# Sheet3_Audio_Out.net
KiCad netlist of a schematic drawn in Altium Designer
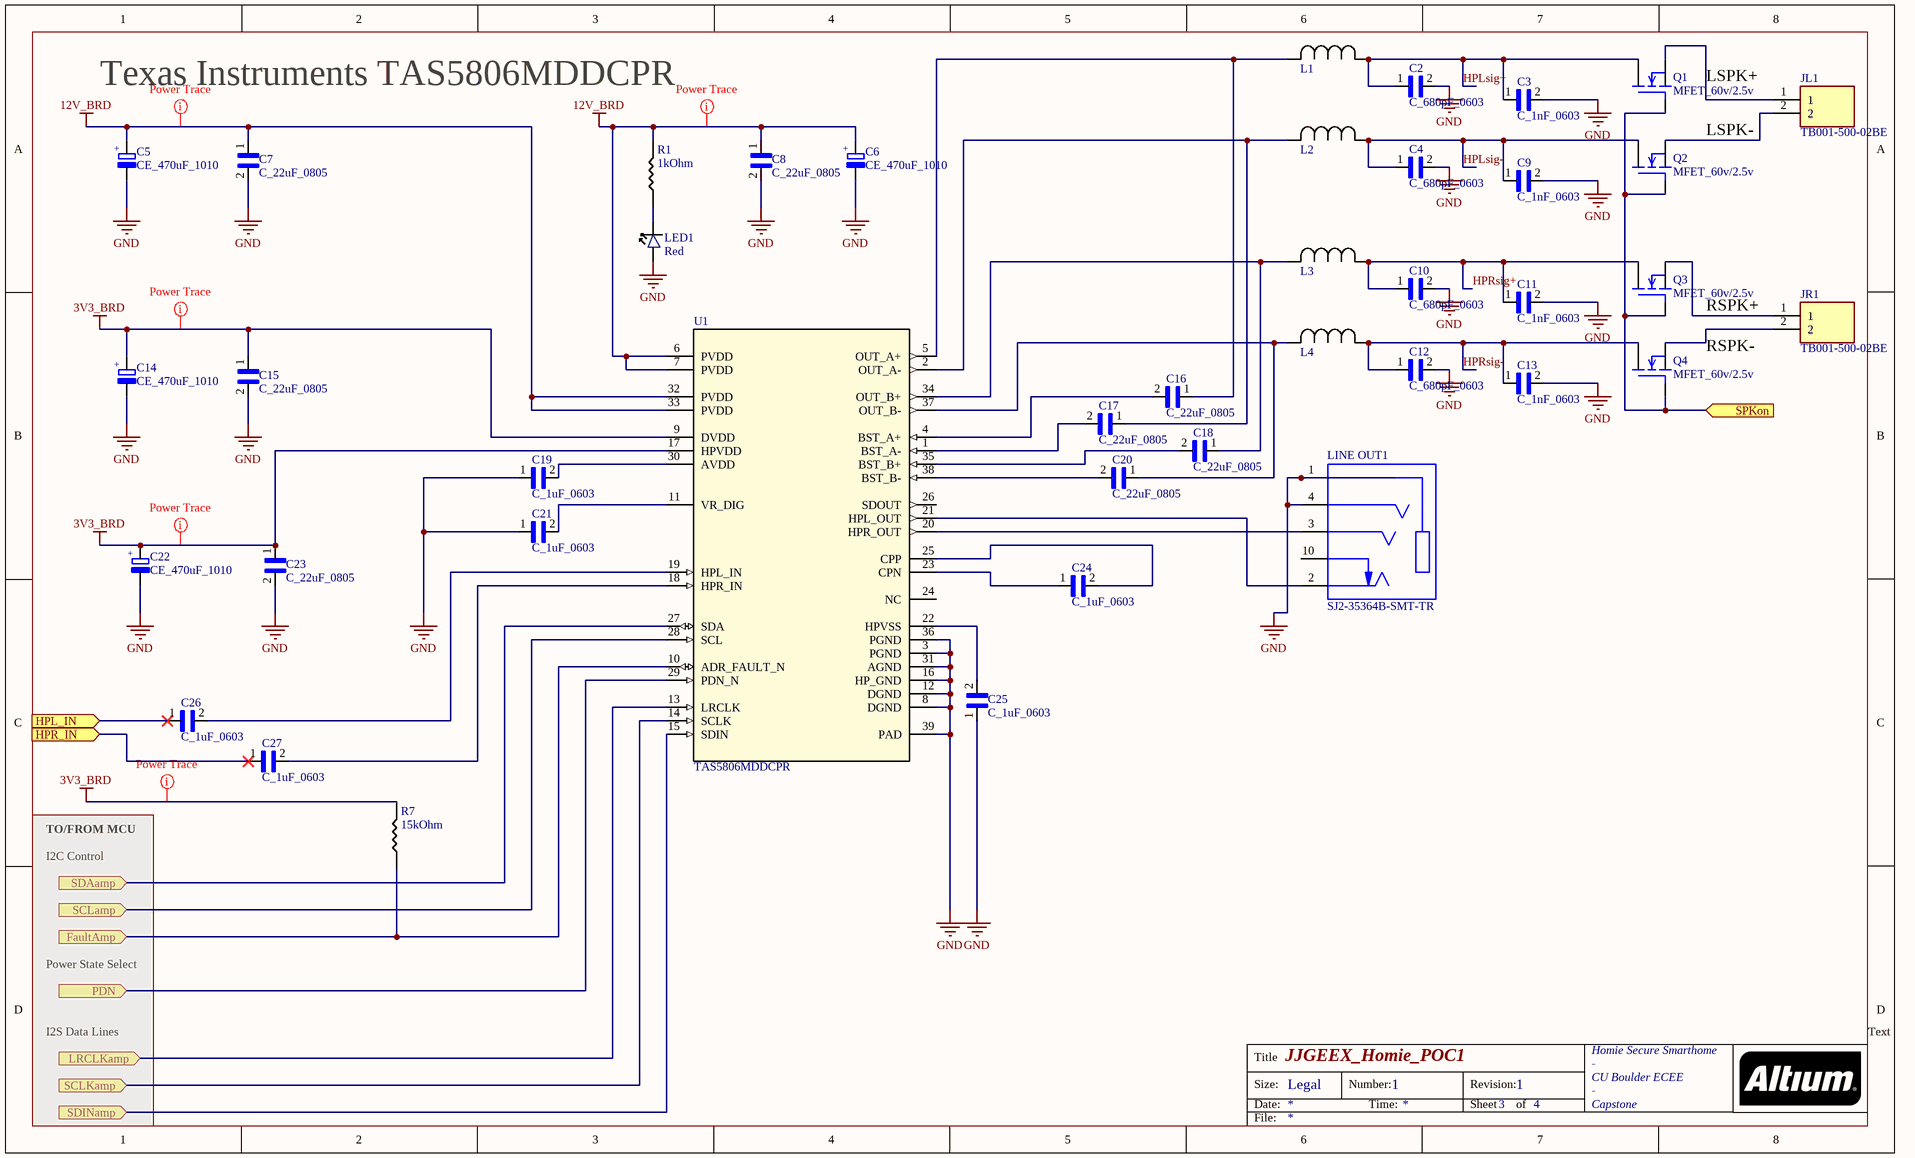
[diagram p0: Sheet3_Audio_Out.SchDoc]

(export (version "E")
  (design (tool "Eeschema 10.0.6"))
  (components
    (comp (ref "C2")
      (value "C_680pF_0603")
      (footprint "CAPC1608X90N")
      (description "680pF ±10% 50V Ceramic Capacitor X7R 0603 (1608 Metric)")
      (fields (field (name "MP") "CL10B684KO8NNNC") (field (name "MF") "Samsung"))
      (libsource (lib "Homie_IntegratedLibraryV2") (part "C_680pF_0603"))
    )
    (comp (ref "C3")
      (value "C_1nF_0603")
      (footprint "CAPC1608X90N")
      (description "1000pF ±10% 50V Ceramic Capacitor X7R 0603 (1608 Metric)")
      (fields (field (name "MP") "CL10B102KB8NNNC") (field (name "MF") "Samsung"))
      (libsource (lib "Homie_IntegratedLibraryV2") (part "C_1nF_0603"))
    )
    (comp (ref "C4")
      (value "C_680pF_0603")
      (footprint "CAPC1608X90N")
      (description "680pF ±10% 50V Ceramic Capacitor X7R 0603 (1608 Metric)")
      (fields (field (name "MP") "CL10B684KO8NNNC") (field (name "MF") "Samsung"))
      (libsource (lib "Homie_IntegratedLibraryV2") (part "C_680pF_0603"))
    )
    (comp (ref "C5")
      (value "CE_470uF_1010")
      (footprint "140CLH-1010")
      (description "Aluminum Electrolytic Capacitors - SMD")
      (fields (field (name "MP") "VZH471M1ETR-1010") (field (name "MF") "Lelon"))
      (libsource (lib "Homie_IntegratedLibraryV2") (part "CE_470uF_1010"))
    )
    (comp (ref "C6")
      (value "CE_470uF_1010")
      (footprint "140CLH-1010")
      (description "Aluminum Electrolytic Capacitors - SMD")
      (fields (field (name "MP") "VZH471M1ETR-1010") (field (name "MF") "Lelon"))
      (libsource (lib "Homie_IntegratedLibraryV2") (part "CE_470uF_1010"))
    )
    (comp (ref "C7")
      (value "C_22uF_0805")
      (footprint "CAPC2012X140N")
      (description "22µF 0805 ±20% 25V Ceramic Capacitor X5R 0805 (2012 Metric)")
      (fields (field (name "MF") "Samsung") (field (name "DIGI-KEY_PART_NUMBER") "1276-2908-1-ND"))
      (libsource (lib "") (part "C_22uF_0805_1"))
    )
    (comp (ref "C8")
      (value "C_22uF_0805")
      (footprint "CAPC2012X140N")
      (description "22µF 0805 ±20% 25V Ceramic Capacitor X5R 0805 (2012 Metric)")
      (fields (field (name "MF") "Samsung") (field (name "DIGI-KEY_PART_NUMBER") "1276-2908-1-ND"))
      (libsource (lib "") (part "C_22uF_0805_1"))
    )
    (comp (ref "C9")
      (value "C_1nF_0603")
      (footprint "CAPC1608X90N")
      (description "1000pF ±10% 50V Ceramic Capacitor X7R 0603 (1608 Metric)")
      (fields (field (name "MP") "CL10B102KB8NNNC") (field (name "MF") "Samsung"))
      (libsource (lib "Homie_IntegratedLibraryV2") (part "C_1nF_0603"))
    )
    (comp (ref "C10")
      (value "C_680pF_0603")
      (footprint "CAPC1608X90N")
      (description "680pF ±10% 50V Ceramic Capacitor X7R 0603 (1608 Metric)")
      (fields (field (name "MP") "CL10B684KO8NNNC") (field (name "MF") "Samsung"))
      (libsource (lib "Homie_IntegratedLibraryV2") (part "C_680pF_0603"))
    )
    (comp (ref "C11")
      (value "C_1nF_0603")
      (footprint "CAPC1608X90N")
      (description "1000pF ±10% 50V Ceramic Capacitor X7R 0603 (1608 Metric)")
      (fields (field (name "MP") "CL10B102KB8NNNC") (field (name "MF") "Samsung"))
      (libsource (lib "Homie_IntegratedLibraryV2") (part "C_1nF_0603"))
    )
    (comp (ref "C12")
      (value "C_680pF_0603")
      (footprint "CAPC1608X90N")
      (description "680pF ±10% 50V Ceramic Capacitor X7R 0603 (1608 Metric)")
      (fields (field (name "MP") "CL10B684KO8NNNC") (field (name "MF") "Samsung"))
      (libsource (lib "Homie_IntegratedLibraryV2") (part "C_680pF_0603"))
    )
    (comp (ref "C13")
      (value "C_1nF_0603")
      (footprint "CAPC1608X90N")
      (description "1000pF ±10% 50V Ceramic Capacitor X7R 0603 (1608 Metric)")
      (fields (field (name "MP") "CL10B102KB8NNNC") (field (name "MF") "Samsung"))
      (libsource (lib "Homie_IntegratedLibraryV2") (part "C_1nF_0603"))
    )
    (comp (ref "C14")
      (value "CE_470uF_1010")
      (footprint "140CLH-1010")
      (description "Aluminum Electrolytic Capacitors - SMD")
      (fields (field (name "MP") "VZH471M1ETR-1010") (field (name "MF") "Lelon"))
      (libsource (lib "Homie_IntegratedLibraryV2") (part "CE_470uF_1010"))
    )
    (comp (ref "C15")
      (value "C_22uF_0805")
      (footprint "CAPC2012X140N")
      (description "22µF 0805 ±20% 25V Ceramic Capacitor X5R 0805 (2012 Metric)")
      (fields (field (name "MF") "Samsung") (field (name "DIGI-KEY_PART_NUMBER") "1276-2908-1-ND"))
      (libsource (lib "") (part "C_22uF_0805_1"))
    )
    (comp (ref "C16")
      (value "C_22uF_0805")
      (footprint "CAPC2012X140N")
      (description "22µF 0805 ±20% 25V Ceramic Capacitor X5R 0805 (2012 Metric)")
      (fields (field (name "MF") "Samsung") (field (name "DIGI-KEY_PART_NUMBER") "1276-2908-1-ND"))
      (libsource (lib "Homie_IntegratedLibraryV2") (part "C_22uF_0805"))
    )
    (comp (ref "C17")
      (value "C_22uF_0805")
      (footprint "CAPC2012X140N")
      (description "22µF 0805 ±20% 25V Ceramic Capacitor X5R 0805 (2012 Metric)")
      (fields (field (name "MF") "Samsung") (field (name "DIGI-KEY_PART_NUMBER") "1276-2908-1-ND"))
      (libsource (lib "Homie_IntegratedLibraryV2") (part "C_22uF_0805"))
    )
    (comp (ref "C18")
      (value "C_22uF_0805")
      (footprint "CAPC2012X140N")
      (description "22µF 0805 ±20% 25V Ceramic Capacitor X5R 0805 (2012 Metric)")
      (fields (field (name "MF") "Samsung") (field (name "DIGI-KEY_PART_NUMBER") "1276-2908-1-ND"))
      (libsource (lib "Homie_IntegratedLibraryV2") (part "C_22uF_0805"))
    )
    (comp (ref "C19")
      (value "C_1uF_0603")
      (footprint "CAPC1608X90N")
      (description "1uF ±10% 50V Ceramic Capacitor X7R 0603 (1608 Metric)")
      (fields (field (name "MP") "CL10A105KB8NNNC") (field (name "MF") "Samsung"))
      (libsource (lib "") (part "C_1uF_0603_1"))
    )
    (comp (ref "C20")
      (value "C_22uF_0805")
      (footprint "CAPC2012X140N")
      (description "22µF 0805 ±20% 25V Ceramic Capacitor X5R 0805 (2012 Metric)")
      (fields (field (name "MF") "Samsung") (field (name "DIGI-KEY_PART_NUMBER") "1276-2908-1-ND"))
      (libsource (lib "Homie_IntegratedLibraryV2") (part "C_22uF_0805"))
    )
    (comp (ref "C21")
      (value "C_1uF_0603")
      (footprint "CAPC1608X90N")
      (description "1uF ±10% 50V Ceramic Capacitor X7R 0603 (1608 Metric)")
      (fields (field (name "MP") "CL10A105KB8NNNC") (field (name "MF") "Samsung"))
      (libsource (lib "") (part "C_1uF_0603_1"))
    )
    (comp (ref "C22")
      (value "CE_470uF_1010")
      (footprint "140CLH-1010")
      (description "Aluminum Electrolytic Capacitors - SMD")
      (fields (field (name "MP") "VZH471M1ETR-1010") (field (name "MF") "Lelon"))
      (libsource (lib "Homie_IntegratedLibraryV2") (part "CE_470uF_1010"))
    )
    (comp (ref "C23")
      (value "C_22uF_0805")
      (footprint "CAPC2012X140N")
      (description "22µF 0805 ±20% 25V Ceramic Capacitor X5R 0805 (2012 Metric)")
      (fields (field (name "MF") "Samsung") (field (name "DIGI-KEY_PART_NUMBER") "1276-2908-1-ND"))
      (libsource (lib "") (part "C_22uF_0805_1"))
    )
    (comp (ref "C24")
      (value "C_1uF_0603")
      (footprint "CAPC1608X90N")
      (description "1uF ±10% 50V Ceramic Capacitor X7R 0603 (1608 Metric)")
      (fields (field (name "MP") "CL10A105KB8NNNC") (field (name "MF") "Samsung"))
      (libsource (lib "") (part "C_1uF_0603_1"))
    )
    (comp (ref "C25")
      (value "C_1uF_0603")
      (footprint "CAPC1608X90N")
      (description "1uF ±10% 50V Ceramic Capacitor X7R 0603 (1608 Metric)")
      (fields (field (name "MP") "CL10A105KB8NNNC") (field (name "MF") "Samsung"))
      (libsource (lib "Homie_IntegratedLibraryV2") (part "C_1uF_0603"))
    )
    (comp (ref "C26")
      (value "C_1uF_0603")
      (footprint "CAPC1608X90N")
      (description "1uF ±10% 50V Ceramic Capacitor X7R 0603 (1608 Metric)")
      (fields (field (name "MP") "CL10A105KB8NNNC") (field (name "MF") "Samsung"))
      (libsource (lib "") (part "C_1uF_0603_1"))
    )
    (comp (ref "C27")
      (value "C_1uF_0603")
      (footprint "CAPC1608X90N")
      (description "1uF ±10% 50V Ceramic Capacitor X7R 0603 (1608 Metric)")
      (fields (field (name "MP") "CL10A105KB8NNNC") (field (name "MF") "Samsung"))
      (libsource (lib "") (part "C_1uF_0603_1"))
    )
    (comp (ref "JL1")
      (value "TB001-500-02BE")
      (footprint "CUI_TB001-500-02BE")
      (description "2~24 Poles, Screw Type, Horizontal, 5.0 Pitch, 22~12 _AWG_, Terminal Block Connector")
      (fields (field (name "MF") "CUI Devices"))
      (libsource (lib "Homie_IntegratedLibraryV3") (part "TB001-500-02BE"))
    )
    (comp (ref "JR1")
      (value "TB001-500-02BE")
      (footprint "CUI_TB001-500-02BE")
      (description "2~24 Poles, Screw Type, Horizontal, 5.0 Pitch, 22~12 _AWG_, Terminal Block Connector")
      (fields (field (name "MF") "CUI Devices"))
      (libsource (lib "Homie_IntegratedLibraryV3") (part "TB001-500-02BE"))
    )
    (comp (ref "L1")
      (value "SDFL1608Q4R7KTF")
      (footprint "L0603")
      (description "4.7uH SDFL1608Q4R7KTF")
      (libsource (lib "Homie_IntegratedLibraryV2") (part "L_4.7uH"))
    )
    (comp (ref "L2")
      (value "SDFL1608Q4R7KTF")
      (footprint "L0603")
      (description "4.7uH SDFL1608Q4R7KTF")
      (libsource (lib "Homie_IntegratedLibraryV2") (part "L_4.7uH"))
    )
    (comp (ref "L3")
      (value "SDFL1608Q4R7KTF")
      (footprint "L0603")
      (description "4.7uH SDFL1608Q4R7KTF")
      (libsource (lib "Homie_IntegratedLibraryV2") (part "L_4.7uH"))
    )
    (comp (ref "L4")
      (value "SDFL1608Q4R7KTF")
      (footprint "L0603")
      (description "4.7uH SDFL1608Q4R7KTF")
      (libsource (lib "Homie_IntegratedLibraryV2") (part "L_4.7uH"))
    )
    (comp (ref "LED1")
      (value "Red")
      (footprint "LED0603-R-RD")
      (description "LIGHT EMITTING DIODES (LED) RED 520~625NM 90~100MCD@20MA TOP VIEW 0603 ROHS")
      (fields (field (name "MFR") "Hubei KENTO Elec") (field (name "Comment") "KT-0603R"))
      (libsource (lib "Homie_IntegratedLibraryV2") (part "LED_RED_0603"))
    )
    (comp (ref "LINE OUT1")
      (value "SJ2-35364B-SMT-TR")
      (footprint "CUI_SJ2-35364B-SMT-TR")
      (description "3.5 mm, Stereo, Right Angle, Surface Mount (SMT), Audio Jack Connector")
      (fields (field (name "MF") "{'manufacturer': u'CUI'}"))
      (libsource (lib "Homie_IntegratedLibraryV3") (part "SJ2-35364B-SMT-TR"))
    )
    (comp (ref "Q1")
      (value "MFET_60v/2.5v")
      (footprint "SOT23")
      (description "N-Channel 60V 200mA _Tc_ 350mW _Tc_ Surface Mount SOT-23-3")
      (fields (field (name "MP") "2N7002") (field (name "MF") "STMicroelectronics"))
      (libsource (lib "Homie_IntegratedLibraryV2") (part "MFET_60v/2.5v"))
    )
    (comp (ref "Q2")
      (value "MFET_60v/2.5v")
      (footprint "SOT23")
      (description "N-Channel 60V 200mA _Tc_ 350mW _Tc_ Surface Mount SOT-23-3")
      (fields (field (name "MP") "2N7002") (field (name "MF") "STMicroelectronics"))
      (libsource (lib "Homie_IntegratedLibraryV2") (part "MFET_60v/2.5v"))
    )
    (comp (ref "Q3")
      (value "MFET_60v/2.5v")
      (footprint "SOT23")
      (description "N-Channel 60V 200mA _Tc_ 350mW _Tc_ Surface Mount SOT-23-3")
      (fields (field (name "MP") "2N7002") (field (name "MF") "STMicroelectronics"))
      (libsource (lib "Homie_IntegratedLibraryV2") (part "MFET_60v/2.5v"))
    )
    (comp (ref "Q4")
      (value "MFET_60v/2.5v")
      (footprint "SOT23")
      (description "N-Channel 60V 200mA _Tc_ 350mW _Tc_ Surface Mount SOT-23-3")
      (fields (field (name "MP") "2N7002") (field (name "MF") "STMicroelectronics"))
      (libsource (lib "Homie_IntegratedLibraryV2") (part "MFET_60v/2.5v"))
    )
    (comp (ref "R1")
      (value "1kOhm")
      (footprint "R0603")
      (description "1kOhm +-1%  0603")
      (fields (field (name "MFR") "Uniroyal") (field (name "Comment") "1 kOhm"))
      (libsource (lib "Homie_IntegratedLibraryV2") (part "R_1kOhm_0603"))
    )
    (comp (ref "R7")
      (value "15kOhm")
      (footprint "R0603")
      (description "15kOhm +-1%")
      (fields (field (name "MFR") "Uniroyal") (field (name "Comment") "15 kOhm"))
      (libsource (lib "Homie_IntegratedLibraryV2") (part "R_15kOhm_0603"))
    )
    (comp (ref "U1")
      (value "TAS5806MDDCPR")
      (footprint "DCP0038A_N")
      (description "TI Amp/DAC")
      (fields
        (field (name "MANUFACTURER") "Texas Instruments")
        (field (name "COPYRIGHT") "Copyright (C) 2018 Accelerated Designs. All rights reserved")
      )
      (libsource (lib "Homie_IntegratedLibraryV3") (part "TAS5806MDDCPR"))
    )
  )
  (nets
    (net (code "1") (name "/FaultAmp") (class "Default")
      (node (ref "R7") (pin "1") (pinfunction "1_1") (pintype "passive"))
      (node (ref "U1") (pin "10") (pinfunction "ADR_FAULT_N_10") (pintype "bidirectional"))
    )
    (net (code "2") (name "/HPL_IN") (class "Default")
      (node (ref "C26") (pin "1") (pinfunction "1_1") (pintype "passive+no_connect"))
    )
    (net (code "3") (name "/HPLsig+") (class "Default")
      (node (ref "C2") (pin "1") (pinfunction "1_1") (pintype "passive"))
      (node (ref "C3") (pin "1") (pinfunction "1_1") (pintype "passive"))
      (node (ref "L1") (pin "1") (pinfunction "1_1") (pintype "passive"))
      (node (ref "Q1") (pin "3") (pinfunction "D_3") (pintype "passive"))
    )
    (net (code "4") (name "/HPLsig-") (class "Default")
      (node (ref "C4") (pin "1") (pinfunction "1_1") (pintype "passive"))
      (node (ref "C9") (pin "1") (pinfunction "1_1") (pintype "passive"))
      (node (ref "L2") (pin "1") (pinfunction "1_1") (pintype "passive"))
      (node (ref "Q2") (pin "3") (pinfunction "D_3") (pintype "passive"))
    )
    (net (code "5") (name "/HPR_IN") (class "Default")
      (node (ref "C27") (pin "1") (pinfunction "1_1") (pintype "passive+no_connect"))
    )
    (net (code "6") (name "/HPRsig+") (class "Default")
      (node (ref "C10") (pin "1") (pinfunction "1_1") (pintype "passive"))
      (node (ref "C11") (pin "1") (pinfunction "1_1") (pintype "passive"))
      (node (ref "L3") (pin "1") (pinfunction "1_1") (pintype "passive"))
      (node (ref "Q3") (pin "3") (pinfunction "D_3") (pintype "passive"))
    )
    (net (code "7") (name "/HPRsig-") (class "Default")
      (node (ref "C12") (pin "1") (pinfunction "1_1") (pintype "passive"))
      (node (ref "C13") (pin "1") (pinfunction "1_1") (pintype "passive"))
      (node (ref "L4") (pin "1") (pinfunction "1_1") (pintype "passive"))
      (node (ref "Q4") (pin "3") (pinfunction "D_3") (pintype "passive"))
    )
    (net (code "8") (name "/LRCLKamp") (class "Default")
      (node (ref "U1") (pin "13") (pinfunction "LRCLK_13") (pintype "input"))
    )
    (net (code "9") (name "/PDN") (class "Default")
      (node (ref "U1") (pin "29") (pinfunction "PDN_N_29") (pintype "input"))
    )
    (net (code "10") (name "/SCLKamp") (class "Default")
      (node (ref "U1") (pin "14") (pinfunction "SCLK_14") (pintype "input"))
    )
    (net (code "11") (name "/SCLamp") (class "Default")
      (node (ref "U1") (pin "28") (pinfunction "SCL_28") (pintype "input"))
    )
    (net (code "12") (name "/SDAamp") (class "Default")
      (node (ref "U1") (pin "27") (pinfunction "SDA_27") (pintype "bidirectional"))
    )
    (net (code "13") (name "/SDINamp") (class "Default")
      (node (ref "U1") (pin "15") (pinfunction "SDIN_15") (pintype "input"))
    )
    (net (code "14") (name "/SPKon") (class "Default")
      (node (ref "Q1") (pin "1") (pinfunction "G_1") (pintype "passive"))
      (node (ref "Q2") (pin "1") (pinfunction "G_1") (pintype "passive"))
      (node (ref "Q3") (pin "1") (pinfunction "G_1") (pintype "passive"))
      (node (ref "Q4") (pin "1") (pinfunction "G_1") (pintype "passive"))
    )
    (net (code "15") (name "3V3_BRD") (class "Default")
      (node (ref "C14") (pin "POS") (pinfunction "POS_POS") (pintype "passive"))
      (node (ref "C15") (pin "1") (pinfunction "1_1") (pintype "passive"))
      (node (ref "C22") (pin "POS") (pinfunction "POS_POS") (pintype "passive"))
      (node (ref "C23") (pin "1") (pinfunction "1_1") (pintype "passive"))
      (node (ref "R7") (pin "2") (pinfunction "2_2") (pintype "passive"))
      (node (ref "U1") (pin "17") (pinfunction "HPVDD_17") (pintype "power_in"))
      (node (ref "U1") (pin "9") (pinfunction "DVDD_9") (pintype "power_in"))
    )
    (net (code "16") (name "12V_BRD") (class "Default")
      (node (ref "C5") (pin "POS") (pinfunction "POS_POS") (pintype "passive"))
      (node (ref "C6") (pin "POS") (pinfunction "POS_POS") (pintype "passive"))
      (node (ref "C7") (pin "1") (pinfunction "1_1") (pintype "passive"))
      (node (ref "C8") (pin "1") (pinfunction "1_1") (pintype "passive"))
      (node (ref "R1") (pin "2") (pinfunction "2_2") (pintype "passive"))
      (node (ref "U1") (pin "32") (pinfunction "PVDD_32") (pintype "power_in"))
      (node (ref "U1") (pin "33") (pinfunction "PVDD_33") (pintype "power_in"))
      (node (ref "U1") (pin "6") (pinfunction "PVDD_6") (pintype "power_in"))
      (node (ref "U1") (pin "7") (pinfunction "PVDD_7") (pintype "power_in"))
    )
    (net (code "17") (name "GND") (class "Default")
      (node (ref "C10") (pin "2") (pinfunction "2_2") (pintype "passive"))
      (node (ref "C11") (pin "2") (pinfunction "2_2") (pintype "passive"))
      (node (ref "C12") (pin "2") (pinfunction "2_2") (pintype "passive"))
      (node (ref "C13") (pin "2") (pinfunction "2_2") (pintype "passive"))
      (node (ref "C14") (pin "NEG") (pinfunction "NEG_NEG") (pintype "passive"))
      (node (ref "C15") (pin "2") (pinfunction "2_2") (pintype "passive"))
      (node (ref "C19") (pin "1") (pinfunction "1_1") (pintype "passive"))
      (node (ref "C2") (pin "2") (pinfunction "2_2") (pintype "passive"))
      (node (ref "C21") (pin "1") (pinfunction "1_1") (pintype "passive"))
      (node (ref "C22") (pin "NEG") (pinfunction "NEG_NEG") (pintype "passive"))
      (node (ref "C23") (pin "2") (pinfunction "2_2") (pintype "passive"))
      (node (ref "C25") (pin "1") (pinfunction "1_1") (pintype "passive"))
      (node (ref "C3") (pin "2") (pinfunction "2_2") (pintype "passive"))
      (node (ref "C4") (pin "2") (pinfunction "2_2") (pintype "passive"))
      (node (ref "C5") (pin "NEG") (pinfunction "NEG_NEG") (pintype "passive"))
      (node (ref "C6") (pin "NEG") (pinfunction "NEG_NEG") (pintype "passive"))
      (node (ref "C7") (pin "2") (pinfunction "2_2") (pintype "passive"))
      (node (ref "C8") (pin "2") (pinfunction "2_2") (pintype "passive"))
      (node (ref "C9") (pin "2") (pinfunction "2_2") (pintype "passive"))
      (node (ref "LED1") (pin "2") (pinfunction "2_2") (pintype "passive"))
      (node (ref "LINE OUT1") (pin "1") (pinfunction "1_1") (pintype "passive"))
      (node (ref "LINE OUT1") (pin "4") (pinfunction "4_4") (pintype "passive"))
      (node (ref "U1") (pin "12") (pinfunction "DGND_12") (pintype "power_in"))
      (node (ref "U1") (pin "16") (pinfunction "HP_GND_16") (pintype "power_in"))
      (node (ref "U1") (pin "3") (pinfunction "PGND_3") (pintype "power_in"))
      (node (ref "U1") (pin "31") (pinfunction "AGND_31") (pintype "power_in"))
      (node (ref "U1") (pin "36") (pinfunction "PGND_36") (pintype "power_in"))
      (node (ref "U1") (pin "39") (pinfunction "PAD_39") (pintype "passive"))
      (node (ref "U1") (pin "8") (pinfunction "DGND_8") (pintype "power_in"))
    )
    (net (code "18") (name "Net-(LED1-Pad1)") (class "Default")
      (node (ref "LED1") (pin "1") (pinfunction "1_1") (pintype "passive"))
      (node (ref "R1") (pin "1") (pinfunction "1_1") (pintype "passive"))
    )
    (net (code "19") (name "Net-(Q1-S)") (class "Default")
      (node (ref "JL1") (pin "1") (pinfunction "1_1") (pintype "passive"))
      (node (ref "Q1") (pin "2") (pinfunction "S_2") (pintype "passive"))
    )
    (net (code "20") (name "Net-(Q2-S)") (class "Default")
      (node (ref "JL1") (pin "2") (pinfunction "2_2") (pintype "passive"))
      (node (ref "Q2") (pin "2") (pinfunction "S_2") (pintype "passive"))
    )
    (net (code "21") (name "Net-(Q3-S)") (class "Default")
      (node (ref "JR1") (pin "1") (pinfunction "1_1") (pintype "passive"))
      (node (ref "Q3") (pin "2") (pinfunction "S_2") (pintype "passive"))
    )
    (net (code "22") (name "Net-(Q4-S)") (class "Default")
      (node (ref "JR1") (pin "2") (pinfunction "2_2") (pintype "passive"))
      (node (ref "Q4") (pin "2") (pinfunction "S_2") (pintype "passive"))
    )
    (net (code "23") (name "Net-(U1-AVDD)") (class "Default")
      (node (ref "C19") (pin "2") (pinfunction "2_2") (pintype "passive"))
      (node (ref "U1") (pin "30") (pinfunction "AVDD_30") (pintype "power_in"))
    )
    (net (code "24") (name "Net-(U1-BST_A+)") (class "Default")
      (node (ref "C16") (pin "2") (pinfunction "2_2") (pintype "passive"))
      (node (ref "U1") (pin "4") (pinfunction "BST_A+_4") (pintype "input"))
    )
    (net (code "25") (name "Net-(U1-BST_A-)") (class "Default")
      (node (ref "C17") (pin "2") (pinfunction "2_2") (pintype "passive"))
      (node (ref "U1") (pin "1") (pinfunction "BST_A-_1") (pintype "input"))
    )
    (net (code "26") (name "Net-(U1-BST_B+)") (class "Default")
      (node (ref "C18") (pin "2") (pinfunction "2_2") (pintype "passive"))
      (node (ref "U1") (pin "35") (pinfunction "BST_B+_35") (pintype "input"))
    )
    (net (code "27") (name "Net-(U1-BST_B-)") (class "Default")
      (node (ref "C20") (pin "2") (pinfunction "2_2") (pintype "passive"))
      (node (ref "U1") (pin "38") (pinfunction "BST_B-_38") (pintype "input"))
    )
    (net (code "28") (name "Net-(U1-CPN)") (class "Default")
      (node (ref "C24") (pin "1") (pinfunction "1_1") (pintype "passive"))
      (node (ref "U1") (pin "23") (pinfunction "CPN_23") (pintype "passive"))
    )
    (net (code "29") (name "Net-(U1-CPP)") (class "Default")
      (node (ref "C24") (pin "2") (pinfunction "2_2") (pintype "passive"))
      (node (ref "U1") (pin "25") (pinfunction "CPP_25") (pintype "passive"))
    )
    (net (code "30") (name "Net-(U1-HPL_IN)") (class "Default")
      (node (ref "C26") (pin "2") (pinfunction "2_2") (pintype "passive"))
      (node (ref "U1") (pin "19") (pinfunction "HPL_IN_19") (pintype "input"))
    )
    (net (code "31") (name "Net-(U1-HPL_OUT)") (class "Default")
      (node (ref "LINE OUT1") (pin "2") (pinfunction "2_2") (pintype "passive"))
      (node (ref "U1") (pin "21") (pinfunction "HPL_OUT_21") (pintype "output"))
    )
    (net (code "32") (name "Net-(U1-HPR_IN)") (class "Default")
      (node (ref "C27") (pin "2") (pinfunction "2_2") (pintype "passive"))
      (node (ref "U1") (pin "18") (pinfunction "HPR_IN_18") (pintype "input"))
    )
    (net (code "33") (name "Net-(U1-HPR_OUT)") (class "Default")
      (node (ref "LINE OUT1") (pin "3") (pinfunction "3_3") (pintype "passive"))
      (node (ref "U1") (pin "20") (pinfunction "HPR_OUT_20") (pintype "output"))
    )
    (net (code "34") (name "Net-(U1-HPVSS)") (class "Default")
      (node (ref "C25") (pin "2") (pinfunction "2_2") (pintype "passive"))
      (node (ref "U1") (pin "22") (pinfunction "HPVSS_22") (pintype "power_in"))
    )
    (net (code "35") (name "Net-(U1-OUT_A+)") (class "Default")
      (node (ref "C16") (pin "1") (pinfunction "1_1") (pintype "passive"))
      (node (ref "L1") (pin "2") (pinfunction "2_2") (pintype "passive"))
      (node (ref "U1") (pin "5") (pinfunction "OUT_A+_5") (pintype "output"))
    )
    (net (code "36") (name "Net-(U1-OUT_A-)") (class "Default")
      (node (ref "C17") (pin "1") (pinfunction "1_1") (pintype "passive"))
      (node (ref "L2") (pin "2") (pinfunction "2_2") (pintype "passive"))
      (node (ref "U1") (pin "2") (pinfunction "OUT_A-_2") (pintype "output"))
    )
    (net (code "37") (name "Net-(U1-OUT_B+)") (class "Default")
      (node (ref "C18") (pin "1") (pinfunction "1_1") (pintype "passive"))
      (node (ref "L3") (pin "2") (pinfunction "2_2") (pintype "passive"))
      (node (ref "U1") (pin "34") (pinfunction "OUT_B+_34") (pintype "output"))
    )
    (net (code "38") (name "Net-(U1-OUT_B-)") (class "Default")
      (node (ref "C20") (pin "1") (pinfunction "1_1") (pintype "passive"))
      (node (ref "L4") (pin "2") (pinfunction "2_2") (pintype "passive"))
      (node (ref "U1") (pin "37") (pinfunction "OUT_B-_37") (pintype "output"))
    )
    (net (code "39") (name "Net-(U1-VR_DIG)") (class "Default")
      (node (ref "C21") (pin "2") (pinfunction "2_2") (pintype "passive"))
      (node (ref "U1") (pin "11") (pinfunction "VR_DIG_11") (pintype "power_in"))
    )
    (net (code "40") (name "unconnected-(LINE OUT1-Pad10)") (class "Default")
      (node (ref "LINE OUT1") (pin "10") (pinfunction "10_10") (pintype "passive"))
    )
    (net (code "41") (name "unconnected-(U1-NC-Pad24)") (class "Default")
      (node (ref "U1") (pin "24") (pinfunction "NC_24") (pintype "passive"))
    )
    (net (code "42") (name "unconnected-(U1-SDOUT-Pad26)") (class "Default")
      (node (ref "U1") (pin "26") (pinfunction "SDOUT_26") (pintype "output"))
    )
  )
)
